# Local_Power_5V_Rev1_1.net
KiCad netlist of a schematic drawn in Altium Designer
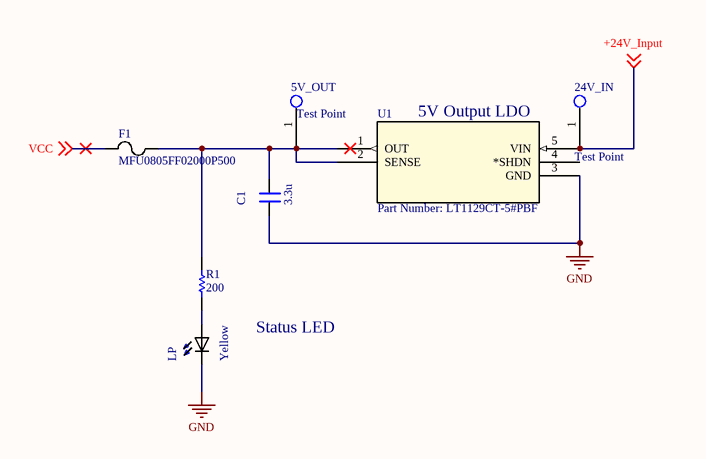
[diagram p0: Local_Power_5V_Rev1.1.SchDoc]

(export (version "E")
  (design (tool "Eeschema 10.0.6"))
  (components
    (comp (ref "5V_OUT")
      (value "Test Point")
      (footprint "Test Point Through-hole")
      (libsource (lib "Test Points") (part "Test Point"))
    )
    (comp (ref "24V_IN")
      (value "Test Point")
      (footprint "Test Point Through-hole")
      (libsource (lib "Test Points") (part "Test Point"))
    )
    (comp (ref "C1")
      (value "3.3u")
      (footprint "*CAPC2012X88N")
      (description "100pF Â±5% 250V Ceramic Capacitor C0G, NP0 0805 _2012 Metric_")
      (fields (field (name "MF") "KEMET") (field (name "DIGI-KEY_PART_NUMBER") "399-15000-1-ND"))
      (libsource (lib "C0805C101JAGAC7800") (part "C0805C101JAGAC7800"))
    )
    (comp (ref "F1")
      (value "MFU0805FF02000P500")
      (footprint "FUS_VISHAY_MFU08")
      (description "No Description Available")
      (fields (field (name "COPYRIGHT") "Copyright (C) 2018 Accelerated Designs. All rights reserved"))
      (libsource (lib "FUSE BOARD MOUNT 2A 32VDC 0805") (part "MFU0805FF02000P5"))
    )
    (comp (ref "LP")
      (value "Yellow")
      (footprint "*DIOC200X125X110_LTST-C171KSKT(Primary)")
      (description "Yellow 2 x 1.25 x 0.8 mm 130Â° Water Clear 50 mcd 2 V LED SMT")
      (fields (field (name "MP") "LTST-C171KSKT") (field (name "DIGI-KEY_PART_NUMBER") "160-1428-1-ND"))
      (libsource (lib "LTST-C171KSKT") (part "LTST-C171KSKT"))
    )
    (comp (ref "R1")
      (value "200")
      (footprint "RESC0805(2012)_M")
      (description "8M06 0.125W 1% 0805 (2012 Metric)  SMD")
      (fields (field (name "POWER") "0.125 W") (field (name "TOLERANCE") "1 %"))
      (libsource (lib "Altium Content Vault") (part "RES"))
    )
    (comp (ref "U1")
      (value "Part Number: LT1129CT-5#PBF")
      (footprint "TO220-5_T")
      (description "No Description Available")
      (fields
        (field (name "MANUFACTURER_PART_NUMBER") "LT1129CT-5#PBF")
        (field (name "COPYRIGHT") "Copyright (C) 2018 Accelerated Designs. All rights reserved")
      )
      (libsource (lib "3") (part "LT1129CT-5#PBF"))
    )
  )
  (nets
    (net (code "1") (name "+24V_Input") (class "Default")
      (node (ref "24V_IN") (pin "1") (pinfunction "1_1") (pintype "passive"))
      (node (ref "U1") (pin "5") (pinfunction "VIN_5") (pintype "input"))
    )
    (net (code "2") (name "GND") (class "Default")
      (node (ref "C1") (pin "1") (pinfunction "1_1") (pintype "passive"))
      (node (ref "LP") (pin "NEG") (pinfunction "NEG_NEG") (pintype "passive"))
      (node (ref "U1") (pin "3") (pinfunction "GND_3") (pintype "power_in"))
    )
    (net (code "3") (name "Net-(LP-PadPOS)") (class "Default")
      (node (ref "LP") (pin "POS") (pinfunction "POS_POS") (pintype "passive"))
      (node (ref "R1") (pin "1") (pinfunction "1_1") (pintype "passive"))
    )
    (net (code "4") (name "Net-(U1-OUT)") (class "Default")
      (node (ref "5V_OUT") (pin "1") (pinfunction "1_1") (pintype "passive"))
      (node (ref "C1") (pin "2") (pinfunction "2_2") (pintype "passive"))
      (node (ref "F1") (pin "2") (pinfunction "2_2") (pintype "passive"))
      (node (ref "R1") (pin "2") (pinfunction "2_2") (pintype "passive"))
      (node (ref "U1") (pin "1") (pinfunction "OUT_1") (pintype "output"))
      (node (ref "U1") (pin "2") (pinfunction "SENSE_2") (pintype "passive"))
    )
    (net (code "5") (name "VCC") (class "Default")
      (node (ref "F1") (pin "1") (pinfunction "1_1") (pintype "passive"))
    )
    (net (code "6") (name "unconnected-(U1-*SHDN-Pad4)") (class "Default")
      (node (ref "U1") (pin "4") (pinfunction "*SHDN_4") (pintype "passive"))
    )
  )
)
